# rip.net
KiCad netlist of a schematic drawn in EAGLE
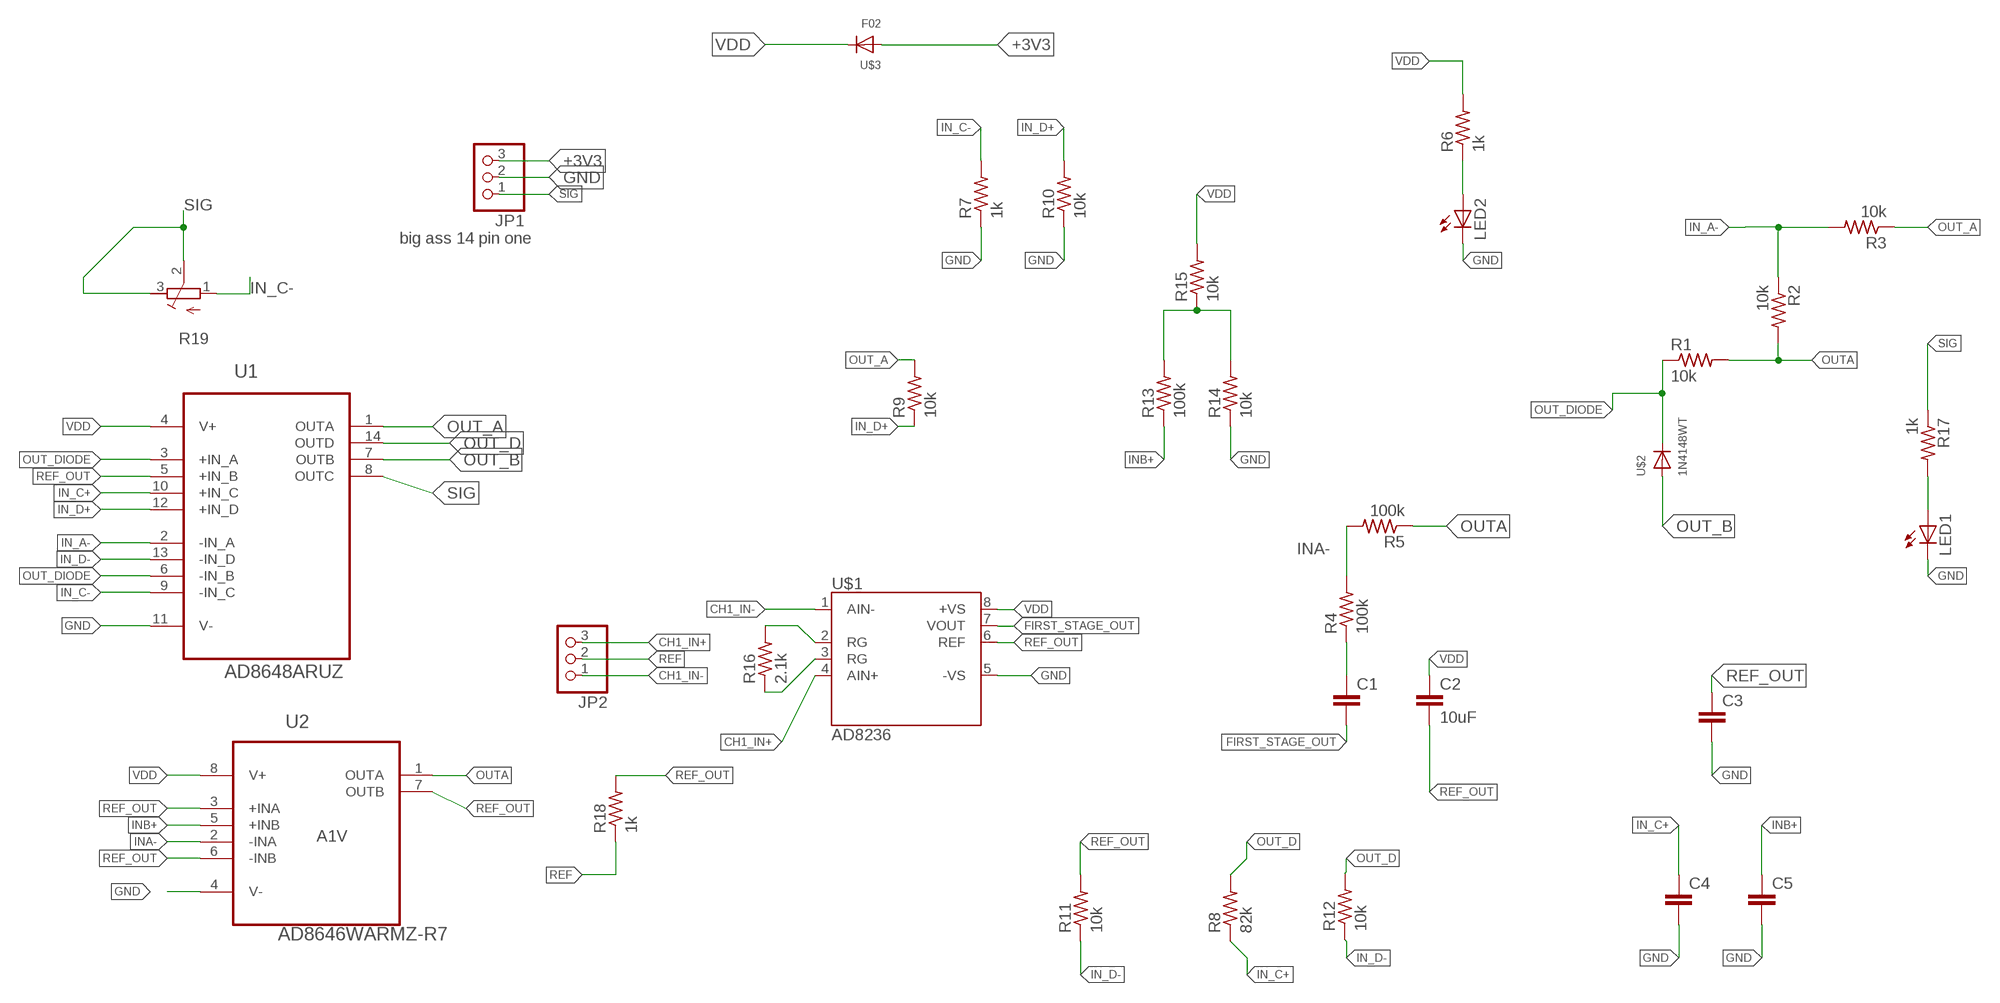
[diagram p0: schematic, sheet 1]

(export (version "E")
  (design (tool "Eeschema 10.0.6"))
  (components
    (comp (ref "C1")
      (value "C-EUC0603")
      (footprint "eagle-import:C0603")
      (libsource (lib "eagle-import") (part "C-EUC0603"))
    )
    (comp (ref "C2")
      (value "10uF")
      (footprint "eagle-import:C0603")
      (libsource (lib "eagle-import") (part "C-EUC0603"))
    )
    (comp (ref "C3")
      (value "C-EUC0603")
      (footprint "eagle-import:C0603")
      (libsource (lib "eagle-import") (part "C-EUC0603"))
    )
    (comp (ref "C4")
      (value "C-EUC0603")
      (footprint "eagle-import:C0603")
      (libsource (lib "eagle-import") (part "C-EUC0603"))
    )
    (comp (ref "C5")
      (value "C-EUC0603")
      (footprint "eagle-import:C0603")
      (libsource (lib "eagle-import") (part "C-EUC0603"))
    )
    (comp (ref "JP1")
      (value "PINHD-1X3")
      (footprint "eagle-import:1X03")
      (libsource (lib "eagle-import") (part "PINHD-1X3"))
    )
    (comp (ref "JP2")
      (value "PINHD-1X3")
      (footprint "eagle-import:1X03")
      (libsource (lib "eagle-import") (part "PINHD-1X3"))
    )
    (comp (ref "LED1")
      (value "LED0603")
      (footprint "eagle-import:LED-0603")
      (libsource (lib "eagle-import") (part "LED0603"))
    )
    (comp (ref "LED2")
      (value "LED0603")
      (footprint "eagle-import:LED-0603")
      (libsource (lib "eagle-import") (part "LED0603"))
    )
    (comp (ref "R1")
      (value "10k")
      (footprint "eagle-import:R0603")
      (libsource (lib "eagle-import") (part "R-US_R0603"))
    )
    (comp (ref "R2")
      (value "10k")
      (footprint "eagle-import:R0603")
      (libsource (lib "eagle-import") (part "R-US_R0603"))
    )
    (comp (ref "R3")
      (value "10k")
      (footprint "eagle-import:R0603")
      (libsource (lib "eagle-import") (part "R-US_R0603"))
    )
    (comp (ref "R4")
      (value "100k")
      (footprint "eagle-import:R0603")
      (libsource (lib "eagle-import") (part "R-US_R0603"))
    )
    (comp (ref "R5")
      (value "100k")
      (footprint "eagle-import:R0603")
      (libsource (lib "eagle-import") (part "R-US_R0603"))
    )
    (comp (ref "R6")
      (value "1k")
      (footprint "eagle-import:R0603")
      (libsource (lib "eagle-import") (part "R-US_R0603"))
    )
    (comp (ref "R7")
      (value "1k")
      (footprint "eagle-import:R0603")
      (libsource (lib "eagle-import") (part "R-US_R0603"))
    )
    (comp (ref "R8")
      (value "82k")
      (footprint "eagle-import:R0603")
      (libsource (lib "eagle-import") (part "R-US_R0603"))
    )
    (comp (ref "R9")
      (value "10k")
      (footprint "eagle-import:R0603")
      (libsource (lib "eagle-import") (part "R-US_R0603"))
    )
    (comp (ref "R10")
      (value "10k")
      (footprint "eagle-import:R0603")
      (libsource (lib "eagle-import") (part "R-US_R0603"))
    )
    (comp (ref "R11")
      (value "10k")
      (footprint "eagle-import:R0603")
      (libsource (lib "eagle-import") (part "R-US_R0603"))
    )
    (comp (ref "R12")
      (value "10k")
      (footprint "eagle-import:R0603")
      (libsource (lib "eagle-import") (part "R-US_R0603"))
    )
    (comp (ref "R13")
      (value "100k")
      (footprint "eagle-import:R0603")
      (libsource (lib "eagle-import") (part "R-US_R0603"))
    )
    (comp (ref "R14")
      (value "10k")
      (footprint "eagle-import:R0603")
      (libsource (lib "eagle-import") (part "R-US_R0603"))
    )
    (comp (ref "R15")
      (value "10k")
      (footprint "eagle-import:R0603")
      (libsource (lib "eagle-import") (part "R-US_R0603"))
    )
    (comp (ref "R16")
      (value "2.1k")
      (footprint "eagle-import:R0603")
      (libsource (lib "eagle-import") (part "R-US_R0603"))
    )
    (comp (ref "R17")
      (value "1k")
      (footprint "eagle-import:R0603")
      (libsource (lib "eagle-import") (part "R-US_R0603"))
    )
    (comp (ref "R18")
      (value "1k")
      (footprint "eagle-import:R0603")
      (libsource (lib "eagle-import") (part "R-US_R0603"))
    )
    (comp (ref "R19")
      (value "R-TRIMM3103")
      (footprint "eagle-import:RTRIM3103")
      (libsource (lib "eagle-import") (part "R-TRIMM3103"))
    )
    (comp (ref "U$1")
      (value "AD8236")
      (footprint "eagle-import:MSOP8")
      (libsource (lib "eagle-import") (part "AD8236"))
    )
    (comp (ref "U$2")
      (value "1N4148WT")
      (footprint "eagle-import:SOD-523")
      (libsource (lib "eagle-import") (part "1N4148WT"))
    )
    (comp (ref "U$3")
      (value "F02")
      (footprint "eagle-import:SOD-523")
      (libsource (lib "eagle-import") (part "F02"))
    )
    (comp (ref "U1")
      (value "AD8648ARUZ")
      (footprint "eagle-import:SOP65P640X120-14N")
      (libsource (lib "eagle-import") (part "AD8648ARUZ"))
    )
    (comp (ref "U2")
      (value "AD8646WARMZ-R7")
      (footprint "eagle-import:SOP65P490X110-8N")
      (libsource (lib "eagle-import") (part "AD8646WARMZ-R7"))
    )
  )
  (nets
    (net (code "1") (name "+3V3") (class "Default")
      (node (ref "JP1") (pin "3") (pinfunction "3_3") (pintype "passive"))
      (node (ref "U$3") (pin "A") (pinfunction "A_A") (pintype "passive"))
    )
    (net (code "2") (name "CH1_IN+") (class "Default")
      (node (ref "JP2") (pin "3") (pinfunction "3_3") (pintype "passive"))
      (node (ref "U$1") (pin "4") (pinfunction "AIN+_4") (pintype "bidirectional"))
    )
    (net (code "3") (name "CH1_IN-") (class "Default")
      (node (ref "JP2") (pin "1") (pinfunction "1_1") (pintype "passive"))
      (node (ref "U$1") (pin "1") (pinfunction "AIN-_1") (pintype "bidirectional"))
    )
    (net (code "4") (name "FIRST_STAGE_OUT") (class "Default")
      (node (ref "C1") (pin "2") (pinfunction "2_2") (pintype "passive"))
      (node (ref "U$1") (pin "7") (pinfunction "VOUT_7") (pintype "bidirectional"))
    )
    (net (code "5") (name "GND") (class "Default")
      (node (ref "C3") (pin "2") (pinfunction "2_2") (pintype "passive"))
      (node (ref "C4") (pin "2") (pinfunction "2_2") (pintype "passive"))
      (node (ref "C5") (pin "2") (pinfunction "2_2") (pintype "passive"))
      (node (ref "JP1") (pin "2") (pinfunction "2_2") (pintype "passive"))
      (node (ref "LED1") (pin "C") (pinfunction "C_C") (pintype "passive"))
      (node (ref "LED2") (pin "C") (pinfunction "C_C") (pintype "passive"))
      (node (ref "R10") (pin "1") (pinfunction "1_1") (pintype "passive"))
      (node (ref "R14") (pin "1") (pinfunction "1_1") (pintype "passive"))
      (node (ref "R7") (pin "1") (pinfunction "1_1") (pintype "passive"))
      (node (ref "U$1") (pin "5") (pinfunction "-VS_5") (pintype "bidirectional"))
      (node (ref "U1") (pin "11") (pinfunction "V-_11") (pintype "power_in"))
      (node (ref "U2") (pin "4") (pinfunction "V-_4") (pintype "power_in"))
    )
    (net (code "6") (name "INA-") (class "Default")
      (node (ref "R4") (pin "2") (pinfunction "2_2") (pintype "passive"))
      (node (ref "R5") (pin "2") (pinfunction "2_2") (pintype "passive"))
      (node (ref "U2") (pin "2") (pinfunction "-INA_2") (pintype "input"))
    )
    (net (code "7") (name "INB+") (class "Default")
      (node (ref "C5") (pin "1") (pinfunction "1_1") (pintype "passive"))
      (node (ref "R13") (pin "1") (pinfunction "1_1") (pintype "passive"))
      (node (ref "U2") (pin "5") (pinfunction "+INB_5") (pintype "input"))
    )
    (net (code "8") (name "IN_A-") (class "Default")
      (node (ref "R2") (pin "1") (pinfunction "1_1") (pintype "passive"))
      (node (ref "R3") (pin "2") (pinfunction "2_2") (pintype "passive"))
      (node (ref "U1") (pin "2") (pinfunction "-IN_A_2") (pintype "input"))
    )
    (net (code "9") (name "IN_C+") (class "Default")
      (node (ref "C4") (pin "1") (pinfunction "1_1") (pintype "passive"))
      (node (ref "R8") (pin "1") (pinfunction "1_1") (pintype "passive"))
      (node (ref "U1") (pin "10") (pinfunction "+IN_C_10") (pintype "input"))
    )
    (net (code "10") (name "IN_C-") (class "Default")
      (node (ref "R19") (pin "1") (pinfunction "A_1") (pintype "passive"))
      (node (ref "R7") (pin "2") (pinfunction "2_2") (pintype "passive"))
      (node (ref "U1") (pin "9") (pinfunction "-IN_C_9") (pintype "input"))
    )
    (net (code "11") (name "IN_D+") (class "Default")
      (node (ref "R10") (pin "2") (pinfunction "2_2") (pintype "passive"))
      (node (ref "R9") (pin "1") (pinfunction "1_1") (pintype "passive"))
      (node (ref "U1") (pin "12") (pinfunction "+IN_D_12") (pintype "input"))
    )
    (net (code "12") (name "IN_D-") (class "Default")
      (node (ref "R11") (pin "1") (pinfunction "1_1") (pintype "passive"))
      (node (ref "R12") (pin "1") (pinfunction "1_1") (pintype "passive"))
      (node (ref "U1") (pin "13") (pinfunction "-IN_D_13") (pintype "input"))
    )
    (net (code "13") (name "Net-(C1-Pad1)") (class "Default")
      (node (ref "C1") (pin "1") (pinfunction "1_1") (pintype "passive"))
      (node (ref "R4") (pin "1") (pinfunction "1_1") (pintype "passive"))
    )
    (net (code "14") (name "Net-(LED1-PadA)") (class "Default")
      (node (ref "LED1") (pin "A") (pinfunction "A_A") (pintype "passive"))
      (node (ref "R17") (pin "2") (pinfunction "2_2") (pintype "passive"))
    )
    (net (code "15") (name "Net-(LED2-PadA)") (class "Default")
      (node (ref "LED2") (pin "A") (pinfunction "A_A") (pintype "passive"))
      (node (ref "R6") (pin "1") (pinfunction "1_1") (pintype "passive"))
    )
    (net (code "16") (name "Net-(R13-Pad2)") (class "Default")
      (node (ref "R13") (pin "2") (pinfunction "2_2") (pintype "passive"))
      (node (ref "R14") (pin "2") (pinfunction "2_2") (pintype "passive"))
      (node (ref "R15") (pin "1") (pinfunction "1_1") (pintype "passive"))
    )
    (net (code "17") (name "Net-(R16-Pad1)") (class "Default")
      (node (ref "R16") (pin "1") (pinfunction "1_1") (pintype "passive"))
      (node (ref "U$1") (pin "3") (pinfunction "RG_3") (pintype "bidirectional"))
    )
    (net (code "18") (name "Net-(R16-Pad2)") (class "Default")
      (node (ref "R16") (pin "2") (pinfunction "2_2") (pintype "passive"))
      (node (ref "U$1") (pin "2") (pinfunction "RG_2") (pintype "bidirectional"))
    )
    (net (code "19") (name "OUTA") (class "Default")
      (node (ref "R1") (pin "2") (pinfunction "2_2") (pintype "passive"))
      (node (ref "R2") (pin "2") (pinfunction "2_2") (pintype "passive"))
      (node (ref "R5") (pin "1") (pinfunction "1_1") (pintype "passive"))
      (node (ref "U2") (pin "1") (pinfunction "OUTA_1") (pintype "output"))
    )
    (net (code "20") (name "OUT_A") (class "Default")
      (node (ref "R3") (pin "1") (pinfunction "1_1") (pintype "passive"))
      (node (ref "R9") (pin "2") (pinfunction "2_2") (pintype "passive"))
      (node (ref "U1") (pin "1") (pinfunction "OUTA_1") (pintype "output"))
    )
    (net (code "21") (name "OUT_B") (class "Default")
      (node (ref "U$2") (pin "A") (pinfunction "A_A") (pintype "passive"))
      (node (ref "U1") (pin "7") (pinfunction "OUTB_7") (pintype "output"))
    )
    (net (code "22") (name "OUT_D") (class "Default")
      (node (ref "R12") (pin "2") (pinfunction "2_2") (pintype "passive"))
      (node (ref "R8") (pin "2") (pinfunction "2_2") (pintype "passive"))
      (node (ref "U1") (pin "14") (pinfunction "OUTD_14") (pintype "output"))
    )
    (net (code "23") (name "OUT_DIODE") (class "Default")
      (node (ref "R1") (pin "1") (pinfunction "1_1") (pintype "passive"))
      (node (ref "U$2") (pin "K") (pinfunction "C_K") (pintype "passive"))
      (node (ref "U1") (pin "3") (pinfunction "+IN_A_3") (pintype "input"))
      (node (ref "U1") (pin "6") (pinfunction "-IN_B_6") (pintype "input"))
    )
    (net (code "24") (name "REF") (class "Default")
      (node (ref "JP2") (pin "2") (pinfunction "2_2") (pintype "passive"))
      (node (ref "R18") (pin "1") (pinfunction "1_1") (pintype "passive"))
    )
    (net (code "25") (name "REF_OUT") (class "Default")
      (node (ref "C2") (pin "2") (pinfunction "2_2") (pintype "passive"))
      (node (ref "C3") (pin "1") (pinfunction "1_1") (pintype "passive"))
      (node (ref "R11") (pin "2") (pinfunction "2_2") (pintype "passive"))
      (node (ref "R18") (pin "2") (pinfunction "2_2") (pintype "passive"))
      (node (ref "U$1") (pin "6") (pinfunction "REF_6") (pintype "bidirectional"))
      (node (ref "U1") (pin "5") (pinfunction "+IN_B_5") (pintype "input"))
      (node (ref "U2") (pin "3") (pinfunction "+INA_3") (pintype "input"))
      (node (ref "U2") (pin "6") (pinfunction "-INB_6") (pintype "input"))
      (node (ref "U2") (pin "7") (pinfunction "OUTB_7") (pintype "output"))
    )
    (net (code "26") (name "SIG") (class "Default")
      (node (ref "JP1") (pin "1") (pinfunction "1_1") (pintype "passive"))
      (node (ref "R17") (pin "1") (pinfunction "1_1") (pintype "passive"))
      (node (ref "R19") (pin "2") (pinfunction "S_2") (pintype "passive"))
      (node (ref "R19") (pin "3") (pinfunction "E_3") (pintype "passive"))
      (node (ref "U1") (pin "8") (pinfunction "OUTC_8") (pintype "output"))
    )
    (net (code "27") (name "VDD") (class "Default")
      (node (ref "C2") (pin "1") (pinfunction "1_1") (pintype "passive"))
      (node (ref "R15") (pin "2") (pinfunction "2_2") (pintype "passive"))
      (node (ref "R6") (pin "2") (pinfunction "2_2") (pintype "passive"))
      (node (ref "U$1") (pin "8") (pinfunction "+VS_8") (pintype "bidirectional"))
      (node (ref "U$3") (pin "K") (pinfunction "C_K") (pintype "passive"))
      (node (ref "U1") (pin "4") (pinfunction "V+_4") (pintype "power_in"))
      (node (ref "U2") (pin "8") (pinfunction "V+_8") (pintype "power_in"))
    )
  )
)
